# 5V_Regulator.net
KiCad netlist of a schematic drawn in Altium Designer
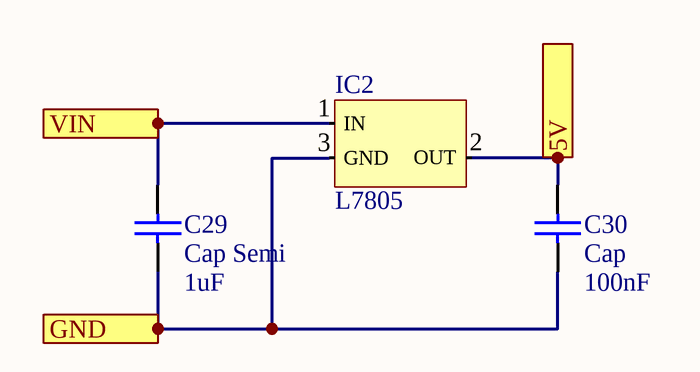
[diagram p0: 5V_Regulator.SchDoc]

(export (version "E")
  (design (tool "Eeschema 10.0.6"))
  (components
    (comp (ref "C29")
      (value "Cap Semi")
      (footprint "0402")
      (description "Multilayer Ceramic Capacitors MLCC - SMD/SMT CGB 0402 16V 1uF JB 20%")
      (fields (field (name "ALTIUM_VALUE") "1uF"))
      (libsource (lib "Miscellaneous Devices") (part "Cap Semi"))
    )
    (comp (ref "C30")
      (value "Cap")
      (footprint "0402")
      (description "Multilayer Ceramic Capacitors MLCC - SMD/SMT 16volts 0.1uF 20% X7R")
      (fields (field (name "ALTIUM_VALUE") "100nF"))
      (libsource (lib "Miscellaneous Devices") (part "Cap"))
    )
    (comp (ref "IC2")
      (value "L7805")
      (footprint "D2PAK")
      (description "Linear Voltage Regulators 5.0V 1.0A Positive")
      (libsource (lib "MainboardSchLib") (part "L7805ACD2T-TR"))
    )
  )
  (nets
    (net (code "1") (name "/5V") (class "Default")
      (node (ref "C30") (pin "2") (pinfunction "2_2") (pintype "passive"))
      (node (ref "IC2") (pin "2") (pinfunction "OUT_2") (pintype "output"))
    )
    (net (code "2") (name "/GND") (class "Default")
      (node (ref "C29") (pin "1") (pinfunction "1_1") (pintype "passive"))
      (node (ref "C30") (pin "1") (pinfunction "1_1") (pintype "passive"))
      (node (ref "IC2") (pin "3") (pinfunction "GND_3") (pintype "power_in"))
    )
    (net (code "3") (name "/VIN") (class "Default")
      (node (ref "C29") (pin "2") (pinfunction "2_2") (pintype "passive"))
      (node (ref "IC2") (pin "1") (pinfunction "IN_1") (pintype "input"))
    )
  )
)
